# Power.net
KiCad netlist of a schematic drawn in Altium Designer
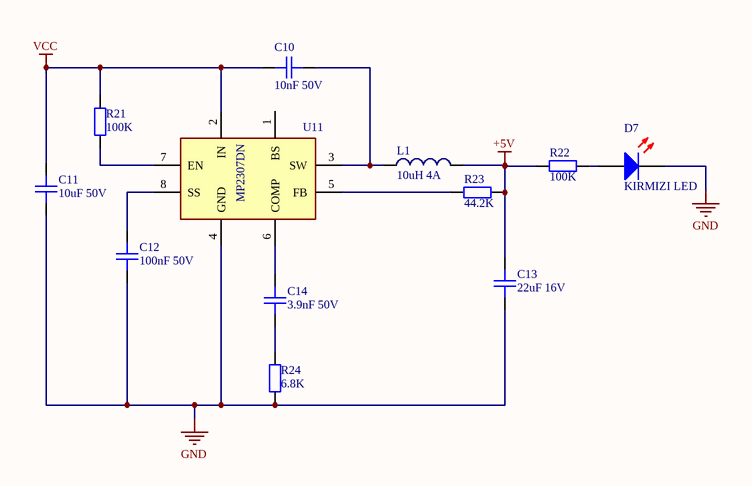
[diagram p0: Power.SchDoc]

(export (version "E")
  (design (tool "Eeschema 10.0.6"))
  (components
    (comp (ref "C10")
      (value "CAP CER 10000PF 50V X7R 0805")
      (footprint "CAP 0805/2012")
      (description "10000pF ±10% 50V Ceramic Capacitor X7R 0805 (2012 Metric)")
      (fields (field (name "DEGER") "10nF 50V"))
      (libsource (lib "PROJE") (part "10nF 50V 0805"))
    )
    (comp (ref "C11")
      (value "CAP CER 10UF 50V X5R 1206")
      (footprint "CAP 1206/3216")
      (description "10µF ±10% 50V Ceramic Capacitor X5R 1206 (3216 Metric)")
      (fields (field (name "DEGER") "10uF 50V"))
      (libsource (lib "PROJE") (part "10uF 50V 1206"))
    )
    (comp (ref "C12")
      (value "CAP CER 0.1UF 50V X7R 0805")
      (footprint "CAP 0805/2012")
      (description "0.1µF ±10% 50V Ceramic Capacitor X7R 0805 (2012 Metric)")
      (fields (field (name "DEGER") "100nF 50V"))
      (libsource (lib "PROJE") (part "100nF 50V 0805"))
    )
    (comp (ref "C13")
      (value "CAP CERAMIC 22UF 16V X7S 20% PAD")
      (footprint "CAP 1206/3216")
      (description "22µF ±20% 16V Ceramic Capacitor X7S 1206 (3216 Metric)")
      (fields (field (name "DEGER") "22uF 16V"))
      (libsource (lib "PROJE") (part "22uF 16V 1206"))
    )
    (comp (ref "C14")
      (value "CAP CER 3900PF 50V X7R 0805")
      (footprint "CAP 0805/2012")
      (description "3900pF ±10% 50V Ceramic Capacitor X7R 0805 (2012 Metric)")
      (fields (field (name "DEGER") "3.9nF 50V"))
      (libsource (lib "PROJE") (part "3.9nF 50V 0805"))
    )
    (comp (ref "D7")
      (value "Red 645nm LED Indication - Discrete 1.8V 0805")
      (footprint "SMD: LED 0805/2012 RED")
      (description "LED RED DIFFUSED 0805 SMD")
      (fields (field (name "DEGER") "KIRMIZI LED"))
      (libsource (lib "PROJE") (part "LED_Kırmızı"))
    )
    (comp (ref "L1")
      (value "FIXED IND 10UH 4A 68 MOHM SMD")
      (footprint "ASPI-0630LR-100M-T15")
      (description "10µH Shielded Molded Inductor 4A 68mOhm Max Nonstandard")
      (fields (field (name "DEGER") "10uH 4A"))
      (libsource (lib "PROJE") (part "10uH 4A"))
    )
    (comp (ref "R21")
      (value "RES SMD 100K OHM 1% 1/8W 0805")
      (footprint "RES_0805")
      (description "100 kOhms ±1% 0.125W, 1/8W Chip Resistor 0805 (2012 Metric) Moisture Resistant Thick Film")
      (fields (field (name "DEGER") "100K"))
      (libsource (lib "PROJE") (part "100K 0805"))
    )
    (comp (ref "R22")
      (value "RES SMD 100K OHM 1% 1/8W 0805")
      (footprint "RES_0805")
      (description "100 kOhms ±1% 0.125W, 1/8W Chip Resistor 0805 (2012 Metric) Moisture Resistant Thick Film")
      (fields (field (name "DEGER") "100K"))
      (libsource (lib "") (part "100K 0805_1"))
    )
    (comp (ref "R23")
      (value "RES SMD 44.2K OHM 1% 1/8W 0805")
      (footprint "RES_0805")
      (description "44.2 kOhms ±1% 0.125W, 1/8W Chip Resistor 0805 (2012 Metric) Moisture Resistant Thick Film")
      (fields (field (name "DEGER") "44.2K"))
      (libsource (lib "PROJE") (part "44.2K 0805"))
    )
    (comp (ref "R24")
      (value "RES SMD 6.8K OHM 1% 1/8W 0805")
      (footprint "RES_0805")
      (description "6.8 kOhms ±1% 0.125W, 1/8W Chip Resistor 0805 (2012 Metric) Moisture Resistant Thick Film")
      (fields (field (name "DEGER") "6.8K"))
      (libsource (lib "PROJE") (part "6.8K 0805"))
    )
    (comp (ref "U11")
      (value "IC REG BUCK ADJUSTABLE 3A 8SOIC")
      (footprint "SOIC8_PAD")
      (fields (field (name "DEGER") "MP2307DN"))
      (libsource (lib "PROJE") (part "MP2307DN"))
    )
  )
  (nets
    (net (code "1") (name "+5V") (class "Default")
      (node (ref "C13") (pin "2") (pinfunction "2_2") (pintype "passive"))
      (node (ref "L1") (pin "2") (pinfunction "2_2") (pintype "passive"))
      (node (ref "R22") (pin "1") (pinfunction "1_1") (pintype "passive"))
      (node (ref "R23") (pin "2") (pinfunction "2_2") (pintype "passive"))
    )
    (net (code "2") (name "GND") (class "Default")
      (node (ref "C11") (pin "1") (pinfunction "1_1") (pintype "passive"))
      (node (ref "C12") (pin "1") (pinfunction "1_1") (pintype "passive"))
      (node (ref "C13") (pin "1") (pinfunction "1_1") (pintype "passive"))
      (node (ref "D7") (pin "2") (pinfunction "K_2") (pintype "passive"))
      (node (ref "R24") (pin "1") (pinfunction "1_1") (pintype "passive"))
      (node (ref "U11") (pin "4") (pinfunction "GND_4") (pintype "passive"))
    )
    (net (code "3") (name "Net-(C14-Pad1)") (class "Default")
      (node (ref "C14") (pin "1") (pinfunction "1_1") (pintype "passive"))
      (node (ref "R24") (pin "2") (pinfunction "2_2") (pintype "passive"))
    )
    (net (code "4") (name "Net-(D7-A)") (class "Default")
      (node (ref "D7") (pin "1") (pinfunction "A_1") (pintype "passive"))
      (node (ref "R22") (pin "2") (pinfunction "2_2") (pintype "passive"))
    )
    (net (code "5") (name "Net-(U11-COMP)") (class "Default")
      (node (ref "C14") (pin "2") (pinfunction "2_2") (pintype "passive"))
      (node (ref "U11") (pin "6") (pinfunction "COMP_6") (pintype "passive"))
    )
    (net (code "6") (name "Net-(U11-EN)") (class "Default")
      (node (ref "R21") (pin "1") (pinfunction "1_1") (pintype "passive"))
      (node (ref "U11") (pin "7") (pinfunction "EN_7") (pintype "passive"))
    )
    (net (code "7") (name "Net-(U11-FB)") (class "Default")
      (node (ref "R23") (pin "1") (pinfunction "1_1") (pintype "passive"))
      (node (ref "U11") (pin "5") (pinfunction "FB_5") (pintype "passive"))
    )
    (net (code "8") (name "Net-(U11-SS)") (class "Default")
      (node (ref "C12") (pin "2") (pinfunction "2_2") (pintype "passive"))
      (node (ref "U11") (pin "8") (pinfunction "SS_8") (pintype "passive"))
    )
    (net (code "9") (name "Net-(U11-SW)") (class "Default")
      (node (ref "C10") (pin "1") (pinfunction "1_1") (pintype "passive"))
      (node (ref "L1") (pin "1") (pinfunction "1_1") (pintype "passive"))
      (node (ref "U11") (pin "3") (pinfunction "SW_3") (pintype "passive"))
    )
    (net (code "10") (name "VCC") (class "Default")
      (node (ref "C10") (pin "2") (pinfunction "2_2") (pintype "passive"))
      (node (ref "C11") (pin "2") (pinfunction "2_2") (pintype "passive"))
      (node (ref "R21") (pin "2") (pinfunction "2_2") (pintype "passive"))
      (node (ref "U11") (pin "2") (pinfunction "IN_2") (pintype "passive"))
    )
    (net (code "11") (name "unconnected-(U11-BS-Pad1)") (class "Default")
      (node (ref "U11") (pin "1") (pinfunction "BS_1") (pintype "passive"))
    )
  )
)
